# Halley2.net
KiCad netlist of a schematic drawn in Altium Designer
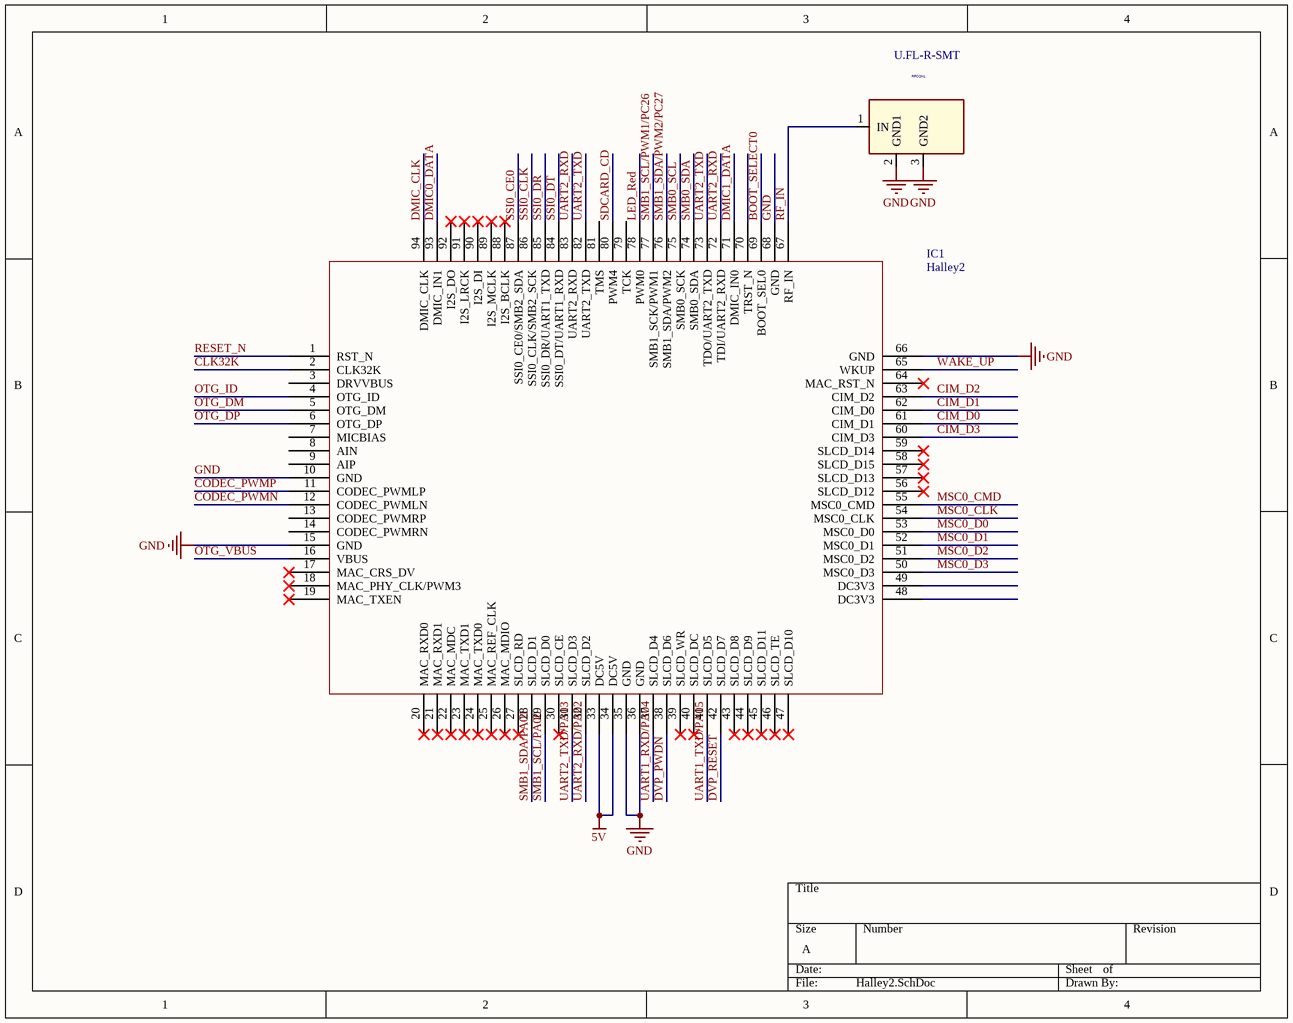
[diagram p0: Halley2.SchDoc]

(export (version "E")
  (design (tool "Eeschema 10.0.6"))
  (components
    (comp (ref "IC1") (value "Halley2") (footprint "Halley2") (libsource (lib "XCore-10") (part "Halley2")))
    (comp (ref "RFCON1")
      (value "U.FL-R-SMT")
      (footprint "ANTENNA_DN007N")
      (libsource (lib "*") (part "ANT_0"))
    )
  )
  (nets
    (net (code "1") (name "/BOOT_SELECT0") (class "Default")
      (node (ref "IC1") (pin "69") (pinfunction "BOOT_SEL0_69") (pintype "passive"))
    )
    (net (code "2") (name "/CIM_D0") (class "Default")
      (node (ref "IC1") (pin "61") (pinfunction "CIM_D1_61") (pintype "passive"))
    )
    (net (code "3") (name "/CIM_D1") (class "Default")
      (node (ref "IC1") (pin "62") (pinfunction "CIM_D0_62") (pintype "passive"))
    )
    (net (code "4") (name "/CIM_D2") (class "Default")
      (node (ref "IC1") (pin "63") (pinfunction "CIM_D2_63") (pintype "passive"))
    )
    (net (code "5") (name "/CIM_D3") (class "Default")
      (node (ref "IC1") (pin "60") (pinfunction "CIM_D3_60") (pintype "passive"))
    )
    (net (code "6") (name "/CLK32K") (class "Default")
      (node (ref "IC1") (pin "2") (pinfunction "CLK32K_2") (pintype "passive"))
    )
    (net (code "7") (name "/CODEC_PWMN") (class "Default")
      (node (ref "IC1") (pin "12") (pinfunction "CODEC_PWMLN_12") (pintype "passive"))
    )
    (net (code "8") (name "/CODEC_PWMP") (class "Default")
      (node (ref "IC1") (pin "11") (pinfunction "CODEC_PWMLP_11") (pintype "passive"))
    )
    (net (code "9") (name "/DMIC0_DATA") (class "Default")
      (node (ref "IC1") (pin "93") (pinfunction "DMIC_IN1_93") (pintype "passive"))
    )
    (net (code "10") (name "/DMIC1_DATA") (class "Default")
      (node (ref "IC1") (pin "71") (pinfunction "DMIC_IN0_71") (pintype "passive"))
    )
    (net (code "11") (name "/DMIC_CLK") (class "Default")
      (node (ref "IC1") (pin "94") (pinfunction "DMIC_CLK_94") (pintype "passive"))
    )
    (net (code "12") (name "/DVP_PWDN") (class "Default")
      (node (ref "IC1") (pin "38") (pinfunction "SLCD_D6_38") (pintype "passive"))
    )
    (net (code "13") (name "/DVP_RESET") (class "Default")
      (node (ref "IC1") (pin "42") (pinfunction "SLCD_D7_42") (pintype "passive"))
    )
    (net (code "14") (name "/LED_Red") (class "Default")
      (node (ref "IC1") (pin "78") (pinfunction "PWM0_78") (pintype "passive"))
    )
    (net (code "15") (name "/MSC0_CLK") (class "Default")
      (node (ref "IC1") (pin "54") (pinfunction "MSC0_CLK_54") (pintype "passive"))
    )
    (net (code "16") (name "/MSC0_CMD") (class "Default")
      (node (ref "IC1") (pin "55") (pinfunction "MSC0_CMD_55") (pintype "passive"))
    )
    (net (code "17") (name "/MSC0_D0") (class "Default")
      (node (ref "IC1") (pin "53") (pinfunction "MSC0_D0_53") (pintype "passive"))
    )
    (net (code "18") (name "/MSC0_D1") (class "Default")
      (node (ref "IC1") (pin "52") (pinfunction "MSC0_D1_52") (pintype "passive"))
    )
    (net (code "19") (name "/MSC0_D2") (class "Default")
      (node (ref "IC1") (pin "51") (pinfunction "MSC0_D2_51") (pintype "passive"))
    )
    (net (code "20") (name "/MSC0_D3") (class "Default")
      (node (ref "IC1") (pin "50") (pinfunction "MSC0_D3_50") (pintype "passive"))
    )
    (net (code "21") (name "/OTG_DM") (class "Default")
      (node (ref "IC1") (pin "5") (pinfunction "OTG_DM_5") (pintype "passive"))
    )
    (net (code "22") (name "/OTG_DP") (class "Default")
      (node (ref "IC1") (pin "6") (pinfunction "OTG_DP_6") (pintype "passive"))
    )
    (net (code "23") (name "/OTG_ID") (class "Default")
      (node (ref "IC1") (pin "4") (pinfunction "OTG_ID_4") (pintype "passive"))
    )
    (net (code "24") (name "/OTG_VBUS") (class "Default")
      (node (ref "IC1") (pin "16") (pinfunction "VBUS_16") (pintype "passive"))
    )
    (net (code "25") (name "/RESET_N") (class "Default")
      (node (ref "IC1") (pin "1") (pinfunction "RST_N_1") (pintype "passive"))
    )
    (net (code "26") (name "/RF_IN") (class "Default")
      (node (ref "IC1") (pin "67") (pinfunction "RF_IN_67") (pintype "passive"))
      (node (ref "RFCON1") (pin "1") (pinfunction "IN_1") (pintype "passive"))
    )
    (net (code "27") (name "/SDCARD_CD") (class "Default")
      (node (ref "IC1") (pin "80") (pinfunction "PWM4_80") (pintype "passive"))
    )
    (net (code "28") (name "/SMB0_SCL") (class "Default")
      (node (ref "IC1") (pin "75") (pinfunction "SMB0_SCK_75") (pintype "passive"))
    )
    (net (code "29") (name "/SMB0_SDA") (class "Default")
      (node (ref "IC1") (pin "74") (pinfunction "SMB0_SDA_74") (pintype "passive"))
    )
    (net (code "30") (name "/SMB1_SCL{slash}PA00") (class "Default")
      (node (ref "IC1") (pin "29") (pinfunction "SLCD_D0_29") (pintype "passive"))
    )
    (net (code "31") (name "/SMB1_SCL{slash}PWM1{slash}PC26") (class "Default")
      (node (ref "IC1") (pin "77") (pinfunction "SMB1_SCK/PWM1_77") (pintype "passive"))
    )
    (net (code "32") (name "/SMB1_SDA{slash}PA01") (class "Default")
      (node (ref "IC1") (pin "28") (pinfunction "SLCD_D1_28") (pintype "passive"))
    )
    (net (code "33") (name "/SMB1_SDA{slash}PWM2{slash}PC27") (class "Default")
      (node (ref "IC1") (pin "76") (pinfunction "SMB1_SDA/PWM2_76") (pintype "passive"))
    )
    (net (code "34") (name "/SSI0_CE0") (class "Default")
      (node (ref "IC1") (pin "87") (pinfunction "SSI0_CE0/SMB2_SDA_87") (pintype "passive"))
    )
    (net (code "35") (name "/SSI0_CLK") (class "Default")
      (node (ref "IC1") (pin "86") (pinfunction "SSI0_CLK/SMB2_SCK_86") (pintype "passive"))
    )
    (net (code "36") (name "/SSI0_DR") (class "Default")
      (node (ref "IC1") (pin "85") (pinfunction "SSI0_DR/UART1_TXD_85") (pintype "passive"))
    )
    (net (code "37") (name "/SSI0_DT") (class "Default")
      (node (ref "IC1") (pin "84") (pinfunction "SSI0_DT/UART1_RXD_84") (pintype "passive"))
    )
    (net (code "38") (name "/UART1_RXD{slash}PA04") (class "Default")
      (node (ref "IC1") (pin "37") (pinfunction "SLCD_D4_37") (pintype "passive"))
    )
    (net (code "39") (name "/UART1_TXD{slash}PA05") (class "Default")
      (node (ref "IC1") (pin "41") (pinfunction "SLCD_D5_41") (pintype "passive"))
    )
    (net (code "40") (name "/UART2_RXD") (class "Default")
      (node (ref "IC1") (pin "72") (pinfunction "TDI/UART2_RXD_72") (pintype "passive"))
      (node (ref "IC1") (pin "83") (pinfunction "UART2_RXD_83") (pintype "passive"))
    )
    (net (code "41") (name "/UART2_RXD{slash}PA02") (class "Default")
      (node (ref "IC1") (pin "32") (pinfunction "SLCD_D2_32") (pintype "passive"))
    )
    (net (code "42") (name "/UART2_TXD") (class "Default")
      (node (ref "IC1") (pin "73") (pinfunction "TDO/UART2_TXD_73") (pintype "passive"))
      (node (ref "IC1") (pin "82") (pinfunction "UART2_TXD_82") (pintype "passive"))
    )
    (net (code "43") (name "/UART2_TXD{slash}PA03") (class "Default")
      (node (ref "IC1") (pin "31") (pinfunction "SLCD_D3_31") (pintype "passive"))
    )
    (net (code "44") (name "/WAKE_UP") (class "Default")
      (node (ref "IC1") (pin "65") (pinfunction "WKUP_65") (pintype "passive"))
    )
    (net (code "45") (name "5V") (class "Default")
      (node (ref "IC1") (pin "33") (pinfunction "DC5V_33") (pintype "passive"))
      (node (ref "IC1") (pin "34") (pinfunction "DC5V_34") (pintype "passive"))
    )
    (net (code "46") (name "GND") (class "Default")
      (node (ref "IC1") (pin "10") (pinfunction "GND_10") (pintype "passive"))
      (node (ref "IC1") (pin "15") (pinfunction "GND_15") (pintype "passive"))
      (node (ref "IC1") (pin "35") (pinfunction "GND_35") (pintype "passive"))
      (node (ref "IC1") (pin "36") (pinfunction "GND_36") (pintype "passive"))
      (node (ref "IC1") (pin "66") (pinfunction "GND_66") (pintype "passive"))
      (node (ref "IC1") (pin "68") (pinfunction "GND_68") (pintype "passive"))
      (node (ref "RFCON1") (pin "2") (pinfunction "GND1_2") (pintype "passive"))
      (node (ref "RFCON1") (pin "3") (pinfunction "GND2_3") (pintype "passive"))
    )
    (net (code "47") (name "unconnected-(IC1-AIN-Pad8)") (class "Default")
      (node (ref "IC1") (pin "8") (pinfunction "AIN_8") (pintype "passive"))
    )
    (net (code "48") (name "unconnected-(IC1-AIP-Pad9)") (class "Default")
      (node (ref "IC1") (pin "9") (pinfunction "AIP_9") (pintype "passive"))
    )
    (net (code "49") (name "unconnected-(IC1-CODEC_PWMRN-Pad14)") (class "Default")
      (node (ref "IC1") (pin "14") (pinfunction "CODEC_PWMRN_14") (pintype "passive"))
    )
    (net (code "50") (name "unconnected-(IC1-CODEC_PWMRP-Pad13)") (class "Default")
      (node (ref "IC1") (pin "13") (pinfunction "CODEC_PWMRP_13") (pintype "passive"))
    )
    (net (code "51") (name "unconnected-(IC1-DC3V3-Pad48)") (class "Default")
      (node (ref "IC1") (pin "48") (pinfunction "DC3V3_48") (pintype "passive"))
    )
    (net (code "52") (name "unconnected-(IC1-DC3V3-Pad49)") (class "Default")
      (node (ref "IC1") (pin "49") (pinfunction "DC3V3_49") (pintype "passive"))
    )
    (net (code "53") (name "unconnected-(IC1-DRVVBUS-Pad3)") (class "Default")
      (node (ref "IC1") (pin "3") (pinfunction "DRVVBUS_3") (pintype "passive"))
    )
    (net (code "54") (name "unconnected-(IC1-I2S_BCLK-Pad88)") (class "Default")
      (node (ref "IC1") (pin "88") (pinfunction "I2S_BCLK_88") (pintype "passive+no_connect"))
    )
    (net (code "55") (name "unconnected-(IC1-I2S_DI-Pad90)") (class "Default")
      (node (ref "IC1") (pin "90") (pinfunction "I2S_DI_90") (pintype "passive+no_connect"))
    )
    (net (code "56") (name "unconnected-(IC1-I2S_DO-Pad92)") (class "Default")
      (node (ref "IC1") (pin "92") (pinfunction "I2S_DO_92") (pintype "passive+no_connect"))
    )
    (net (code "57") (name "unconnected-(IC1-I2S_LRCK-Pad91)") (class "Default")
      (node (ref "IC1") (pin "91") (pinfunction "I2S_LRCK_91") (pintype "passive+no_connect"))
    )
    (net (code "58") (name "unconnected-(IC1-I2S_MCLK-Pad89)") (class "Default")
      (node (ref "IC1") (pin "89") (pinfunction "I2S_MCLK_89") (pintype "passive+no_connect"))
    )
    (net (code "59") (name "unconnected-(IC1-MAC_CRS_DV-Pad17)") (class "Default")
      (node (ref "IC1") (pin "17") (pinfunction "MAC_CRS_DV_17") (pintype "passive+no_connect"))
    )
    (net (code "60") (name "unconnected-(IC1-MAC_MDC-Pad22)") (class "Default")
      (node (ref "IC1") (pin "22") (pinfunction "MAC_MDC_22") (pintype "passive+no_connect"))
    )
    (net (code "61") (name "unconnected-(IC1-MAC_MDIO-Pad26)") (class "Default")
      (node (ref "IC1") (pin "26") (pinfunction "MAC_MDIO_26") (pintype "passive+no_connect"))
    )
    (net (code "62") (name "unconnected-(IC1-MAC_PHY_CLK{slash}PWM3-Pad18)") (class "Default")
      (node (ref "IC1") (pin "18") (pinfunction "MAC_PHY_CLK/PWM3_18") (pintype "passive+no_connect"))
    )
    (net (code "63") (name "unconnected-(IC1-MAC_REF_CLK-Pad25)") (class "Default")
      (node (ref "IC1") (pin "25") (pinfunction "MAC_REF_CLK_25") (pintype "passive+no_connect"))
    )
    (net (code "64") (name "unconnected-(IC1-MAC_RST_N-Pad64)") (class "Default")
      (node (ref "IC1") (pin "64") (pinfunction "MAC_RST_N_64") (pintype "passive+no_connect"))
    )
    (net (code "65") (name "unconnected-(IC1-MAC_RXD0-Pad20)") (class "Default")
      (node (ref "IC1") (pin "20") (pinfunction "MAC_RXD0_20") (pintype "passive+no_connect"))
    )
    (net (code "66") (name "unconnected-(IC1-MAC_RXD1-Pad21)") (class "Default")
      (node (ref "IC1") (pin "21") (pinfunction "MAC_RXD1_21") (pintype "passive+no_connect"))
    )
    (net (code "67") (name "unconnected-(IC1-MAC_TXD0-Pad24)") (class "Default")
      (node (ref "IC1") (pin "24") (pinfunction "MAC_TXD0_24") (pintype "passive+no_connect"))
    )
    (net (code "68") (name "unconnected-(IC1-MAC_TXD1-Pad23)") (class "Default")
      (node (ref "IC1") (pin "23") (pinfunction "MAC_TXD1_23") (pintype "passive+no_connect"))
    )
    (net (code "69") (name "unconnected-(IC1-MAC_TXEN-Pad19)") (class "Default")
      (node (ref "IC1") (pin "19") (pinfunction "MAC_TXEN_19") (pintype "passive+no_connect"))
    )
    (net (code "70") (name "unconnected-(IC1-MICBIAS-Pad7)") (class "Default")
      (node (ref "IC1") (pin "7") (pinfunction "MICBIAS_7") (pintype "passive"))
    )
    (net (code "71") (name "unconnected-(IC1-SLCD_CE-Pad30)") (class "Default")
      (node (ref "IC1") (pin "30") (pinfunction "SLCD_CE_30") (pintype "passive+no_connect"))
    )
    (net (code "72") (name "unconnected-(IC1-SLCD_D8-Pad43)") (class "Default")
      (node (ref "IC1") (pin "43") (pinfunction "SLCD_D8_43") (pintype "passive+no_connect"))
    )
    (net (code "73") (name "unconnected-(IC1-SLCD_D9-Pad44)") (class "Default")
      (node (ref "IC1") (pin "44") (pinfunction "SLCD_D9_44") (pintype "passive+no_connect"))
    )
    (net (code "74") (name "unconnected-(IC1-SLCD_D10-Pad47)") (class "Default")
      (node (ref "IC1") (pin "47") (pinfunction "SLCD_D10_47") (pintype "passive+no_connect"))
    )
    (net (code "75") (name "unconnected-(IC1-SLCD_D11-Pad45)") (class "Default")
      (node (ref "IC1") (pin "45") (pinfunction "SLCD_D11_45") (pintype "passive+no_connect"))
    )
    (net (code "76") (name "unconnected-(IC1-SLCD_D12-Pad56)") (class "Default")
      (node (ref "IC1") (pin "56") (pinfunction "SLCD_D12_56") (pintype "passive+no_connect"))
    )
    (net (code "77") (name "unconnected-(IC1-SLCD_D13-Pad57)") (class "Default")
      (node (ref "IC1") (pin "57") (pinfunction "SLCD_D13_57") (pintype "passive+no_connect"))
    )
    (net (code "78") (name "unconnected-(IC1-SLCD_D14-Pad59)") (class "Default")
      (node (ref "IC1") (pin "59") (pinfunction "SLCD_D14_59") (pintype "passive+no_connect"))
    )
    (net (code "79") (name "unconnected-(IC1-SLCD_D15-Pad58)") (class "Default")
      (node (ref "IC1") (pin "58") (pinfunction "SLCD_D15_58") (pintype "passive+no_connect"))
    )
    (net (code "80") (name "unconnected-(IC1-SLCD_DC-Pad40)") (class "Default")
      (node (ref "IC1") (pin "40") (pinfunction "SLCD_DC_40") (pintype "passive+no_connect"))
    )
    (net (code "81") (name "unconnected-(IC1-SLCD_RD-Pad27)") (class "Default")
      (node (ref "IC1") (pin "27") (pinfunction "SLCD_RD_27") (pintype "passive+no_connect"))
    )
    (net (code "82") (name "unconnected-(IC1-SLCD_TE-Pad46)") (class "Default")
      (node (ref "IC1") (pin "46") (pinfunction "SLCD_TE_46") (pintype "passive+no_connect"))
    )
    (net (code "83") (name "unconnected-(IC1-SLCD_WR-Pad39)") (class "Default")
      (node (ref "IC1") (pin "39") (pinfunction "SLCD_WR_39") (pintype "passive+no_connect"))
    )
    (net (code "84") (name "unconnected-(IC1-TCK-Pad79)") (class "Default")
      (node (ref "IC1") (pin "79") (pinfunction "TCK_79") (pintype "passive"))
    )
    (net (code "85") (name "unconnected-(IC1-TMS-Pad81)") (class "Default")
      (node (ref "IC1") (pin "81") (pinfunction "TMS_81") (pintype "passive"))
    )
    (net (code "86") (name "unconnected-(IC1-TRST_N-Pad70)") (class "Default")
      (node (ref "IC1") (pin "70") (pinfunction "TRST_N_70") (pintype "passive"))
    )
  )
)
